# lighthouse.net
KiCad netlist of a schematic drawn in EAGLE
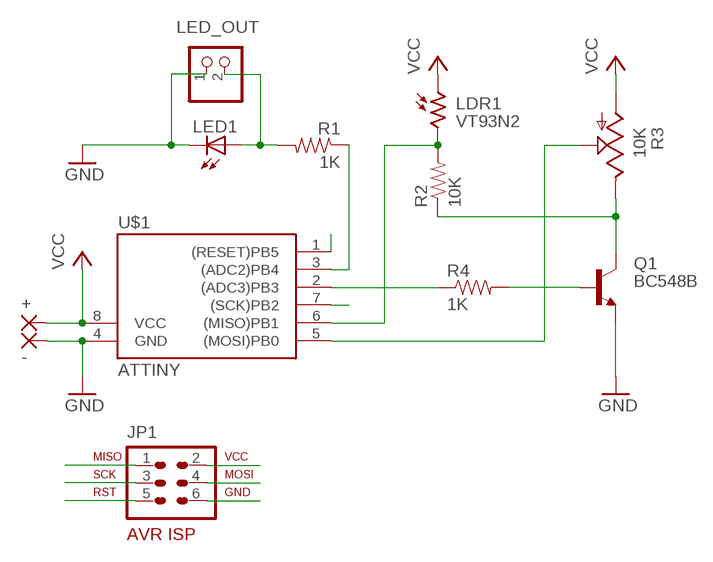
[diagram p0: schematic, sheet 1]

(export (version "E")
  (design (tool "Eeschema 10.0.6"))
  (components
    (comp (ref "+")
      (value "PAD-TERMINAL")
      (footprint "eagle-import:2,54_1,1")
      (libsource (lib "eagle-import") (part "PAD-TERMINAL"))
    )
    (comp (ref "-")
      (value "PAD-TERMINAL")
      (footprint "eagle-import:2,54_1,1")
      (libsource (lib "eagle-import") (part "PAD-TERMINAL"))
    )
    (comp (ref "JP1")
      (value "AVR-ISP-6VERT")
      (footprint "eagle-import:AVR-ISP-6")
      (libsource (lib "eagle-import") (part "AVR-ISP-6VERT"))
    )
    (comp (ref "LDR1")
      (value "VT93N2")
      (footprint "eagle-import:VT900")
      (libsource (lib "eagle-import") (part "VT93N2"))
    )
    (comp (ref "LED1")
      (value "LED-3MM-NO_SILK")
      (footprint "eagle-import:LED3MM-NS")
      (libsource (lib "eagle-import") (part "LED-3MM-NO_SILK"))
    )
    (comp (ref "LED_OUT")
      (value "PINHD-1X2")
      (footprint "eagle-import:1X02")
      (fields (field (name "MPN") "BC237B"))
      (libsource (lib "eagle-import") (part "PINHD-1X2"))
    )
    (comp (ref "Q1")
      (value "BC548B")
      (footprint "eagle-import:TO92-EBC")
      (libsource (lib "eagle-import") (part "BC548B"))
    )
    (comp (ref "R1")
      (value "1K")
      (footprint "eagle-import:AXIAL-0.4")
      (libsource (lib "eagle-import") (part "RESISTORPTH-1/4W"))
    )
    (comp (ref "R2")
      (value "10K")
      (footprint "eagle-import:AXIAL-0.4")
      (libsource (lib "eagle-import") (part "RESISTORPTH-1/4W"))
    )
    (comp (ref "R3")
      (value "10K")
      (footprint "eagle-import:CA6H")
      (libsource (lib "eagle-import") (part "TRIM_US-CA6H"))
    )
    (comp (ref "R4")
      (value "1K")
      (footprint "eagle-import:AXIAL-0.4")
      (libsource (lib "eagle-import") (part "RESISTORPTH-1/4W"))
    )
    (comp (ref "U$1")
      (value "ATTINY")
      (footprint "eagle-import:DIL08")
      (libsource (lib "eagle-import") (part "TINY138P3"))
    )
  )
  (nets
    (net (code "1") (name "/MISO") (class "Default")
      (node (ref "JP1") (pin "1") (pinfunction "1_1") (pintype "passive"))
      (node (ref "LDR1") (pin "2") (pinfunction "2_2") (pintype "passive"))
      (node (ref "R2") (pin "P$2") (pinfunction "2_P$2") (pintype "passive"))
      (node (ref "U$1") (pin "6") (pinfunction "(MISO)PB1_6") (pintype "bidirectional"))
    )
    (net (code "2") (name "/MOSI") (class "Default")
      (node (ref "JP1") (pin "4") (pinfunction "4_4") (pintype "passive"))
      (node (ref "R3") (pin "S") (pinfunction "S_S") (pintype "passive"))
      (node (ref "U$1") (pin "5") (pinfunction "(MOSI)PB0_5") (pintype "bidirectional"))
    )
    (net (code "3") (name "/RST") (class "Default")
      (node (ref "JP1") (pin "5") (pinfunction "5_5") (pintype "passive"))
      (node (ref "U$1") (pin "1") (pinfunction "(RESET)PB5_1") (pintype "bidirectional"))
    )
    (net (code "4") (name "/SCK") (class "Default")
      (node (ref "JP1") (pin "3") (pinfunction "3_3") (pintype "passive"))
      (node (ref "U$1") (pin "7") (pinfunction "(SCK)PB2_7") (pintype "bidirectional"))
    )
    (net (code "5") (name "GND") (class "Default")
      (node (ref "-") (pin "1") (pinfunction "P_1") (pintype "passive"))
      (node (ref "JP1") (pin "6") (pinfunction "6_6") (pintype "passive"))
      (node (ref "LED1") (pin "K") (pinfunction "C_K") (pintype "passive"))
      (node (ref "LED_OUT") (pin "1") (pinfunction "1_1") (pintype "passive"))
      (node (ref "Q1") (pin "E") (pinfunction "E_E") (pintype "passive"))
      (node (ref "U$1") (pin "4") (pinfunction "GND_4") (pintype "power_in"))
    )
    (net (code "6") (name "Net-(R1-1)") (class "Default")
      (node (ref "R1") (pin "P$1") (pinfunction "1_P$1") (pintype "passive"))
      (node (ref "U$1") (pin "3") (pinfunction "(ADC2)PB4_3") (pintype "bidirectional"))
    )
    (net (code "7") (name "Net-(R1-2)") (class "Default")
      (node (ref "LED1") (pin "A") (pinfunction "A_A") (pintype "passive"))
      (node (ref "LED_OUT") (pin "2") (pinfunction "2_2") (pintype "passive"))
      (node (ref "R1") (pin "P$2") (pinfunction "2_P$2") (pintype "passive"))
    )
    (net (code "8") (name "Net-(R2-1)") (class "Default")
      (node (ref "Q1") (pin "C") (pinfunction "C_C") (pintype "passive"))
      (node (ref "R2") (pin "P$1") (pinfunction "1_P$1") (pintype "passive"))
      (node (ref "R3") (pin "E") (pinfunction "E_E") (pintype "passive"))
    )
    (net (code "9") (name "Net-(R4-1)") (class "Default")
      (node (ref "R4") (pin "P$1") (pinfunction "1_P$1") (pintype "passive"))
      (node (ref "U$1") (pin "2") (pinfunction "(ADC3)PB3_2") (pintype "bidirectional"))
    )
    (net (code "10") (name "Net-(R4-2)") (class "Default")
      (node (ref "Q1") (pin "B") (pinfunction "B_B") (pintype "passive"))
      (node (ref "R4") (pin "P$2") (pinfunction "2_P$2") (pintype "passive"))
    )
    (net (code "11") (name "VCC") (class "Default")
      (node (ref "+") (pin "1") (pinfunction "P_1") (pintype "passive"))
      (node (ref "JP1") (pin "2") (pinfunction "2_2") (pintype "passive"))
      (node (ref "LDR1") (pin "1") (pinfunction "1_1") (pintype "passive"))
      (node (ref "R3") (pin "A") (pinfunction "A_A") (pintype "passive"))
      (node (ref "U$1") (pin "8") (pinfunction "VCC_8") (pintype "power_in"))
    )
  )
)
